# tm4cShield_v2_0.net
KiCad netlist of a schematic drawn in EAGLE
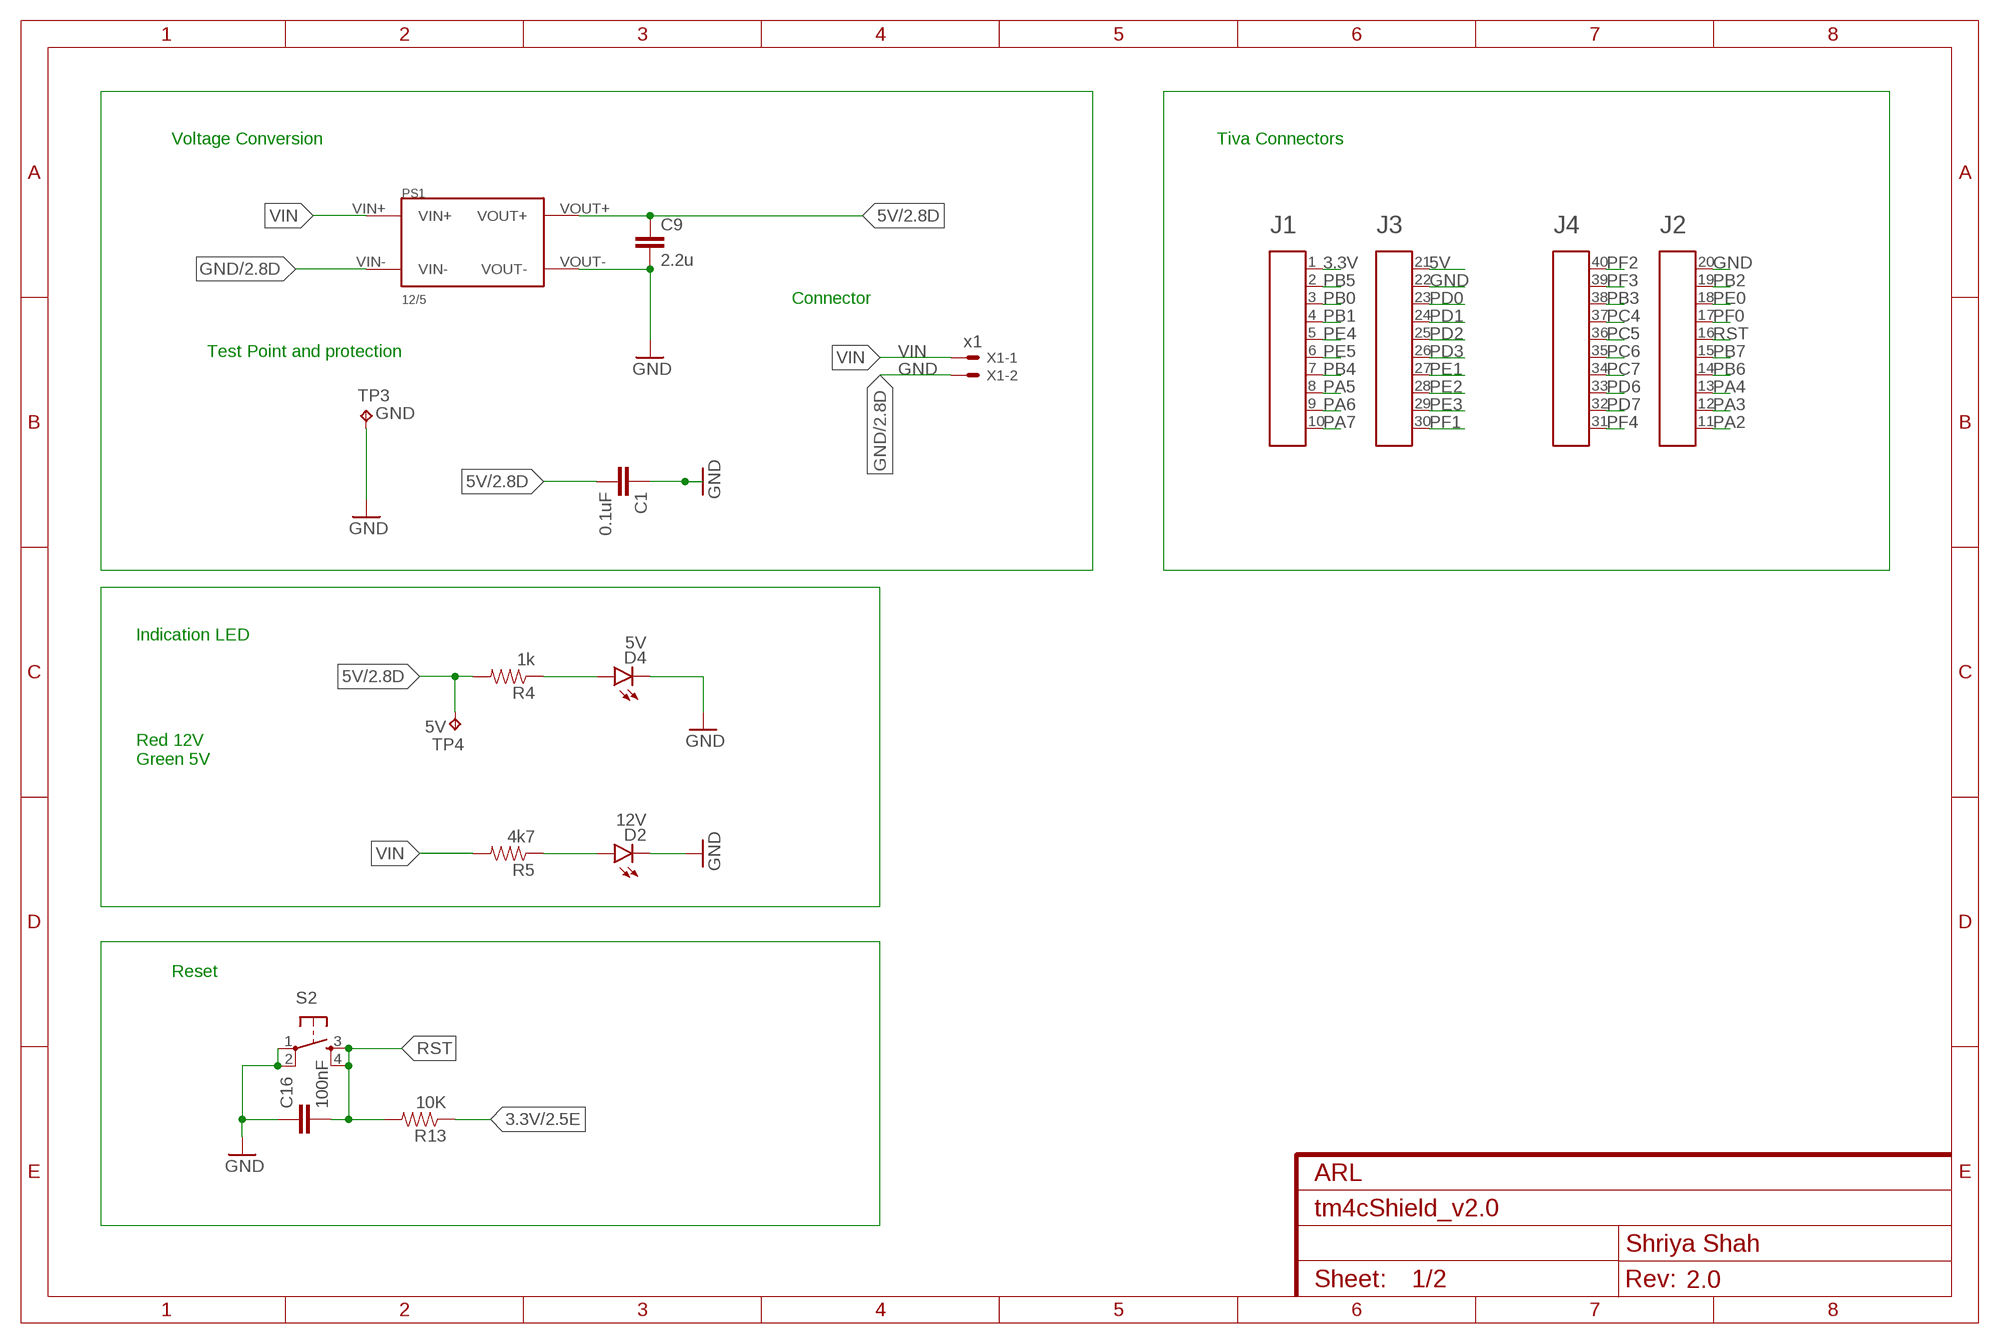
[diagram p0: schematic, sheet 1]
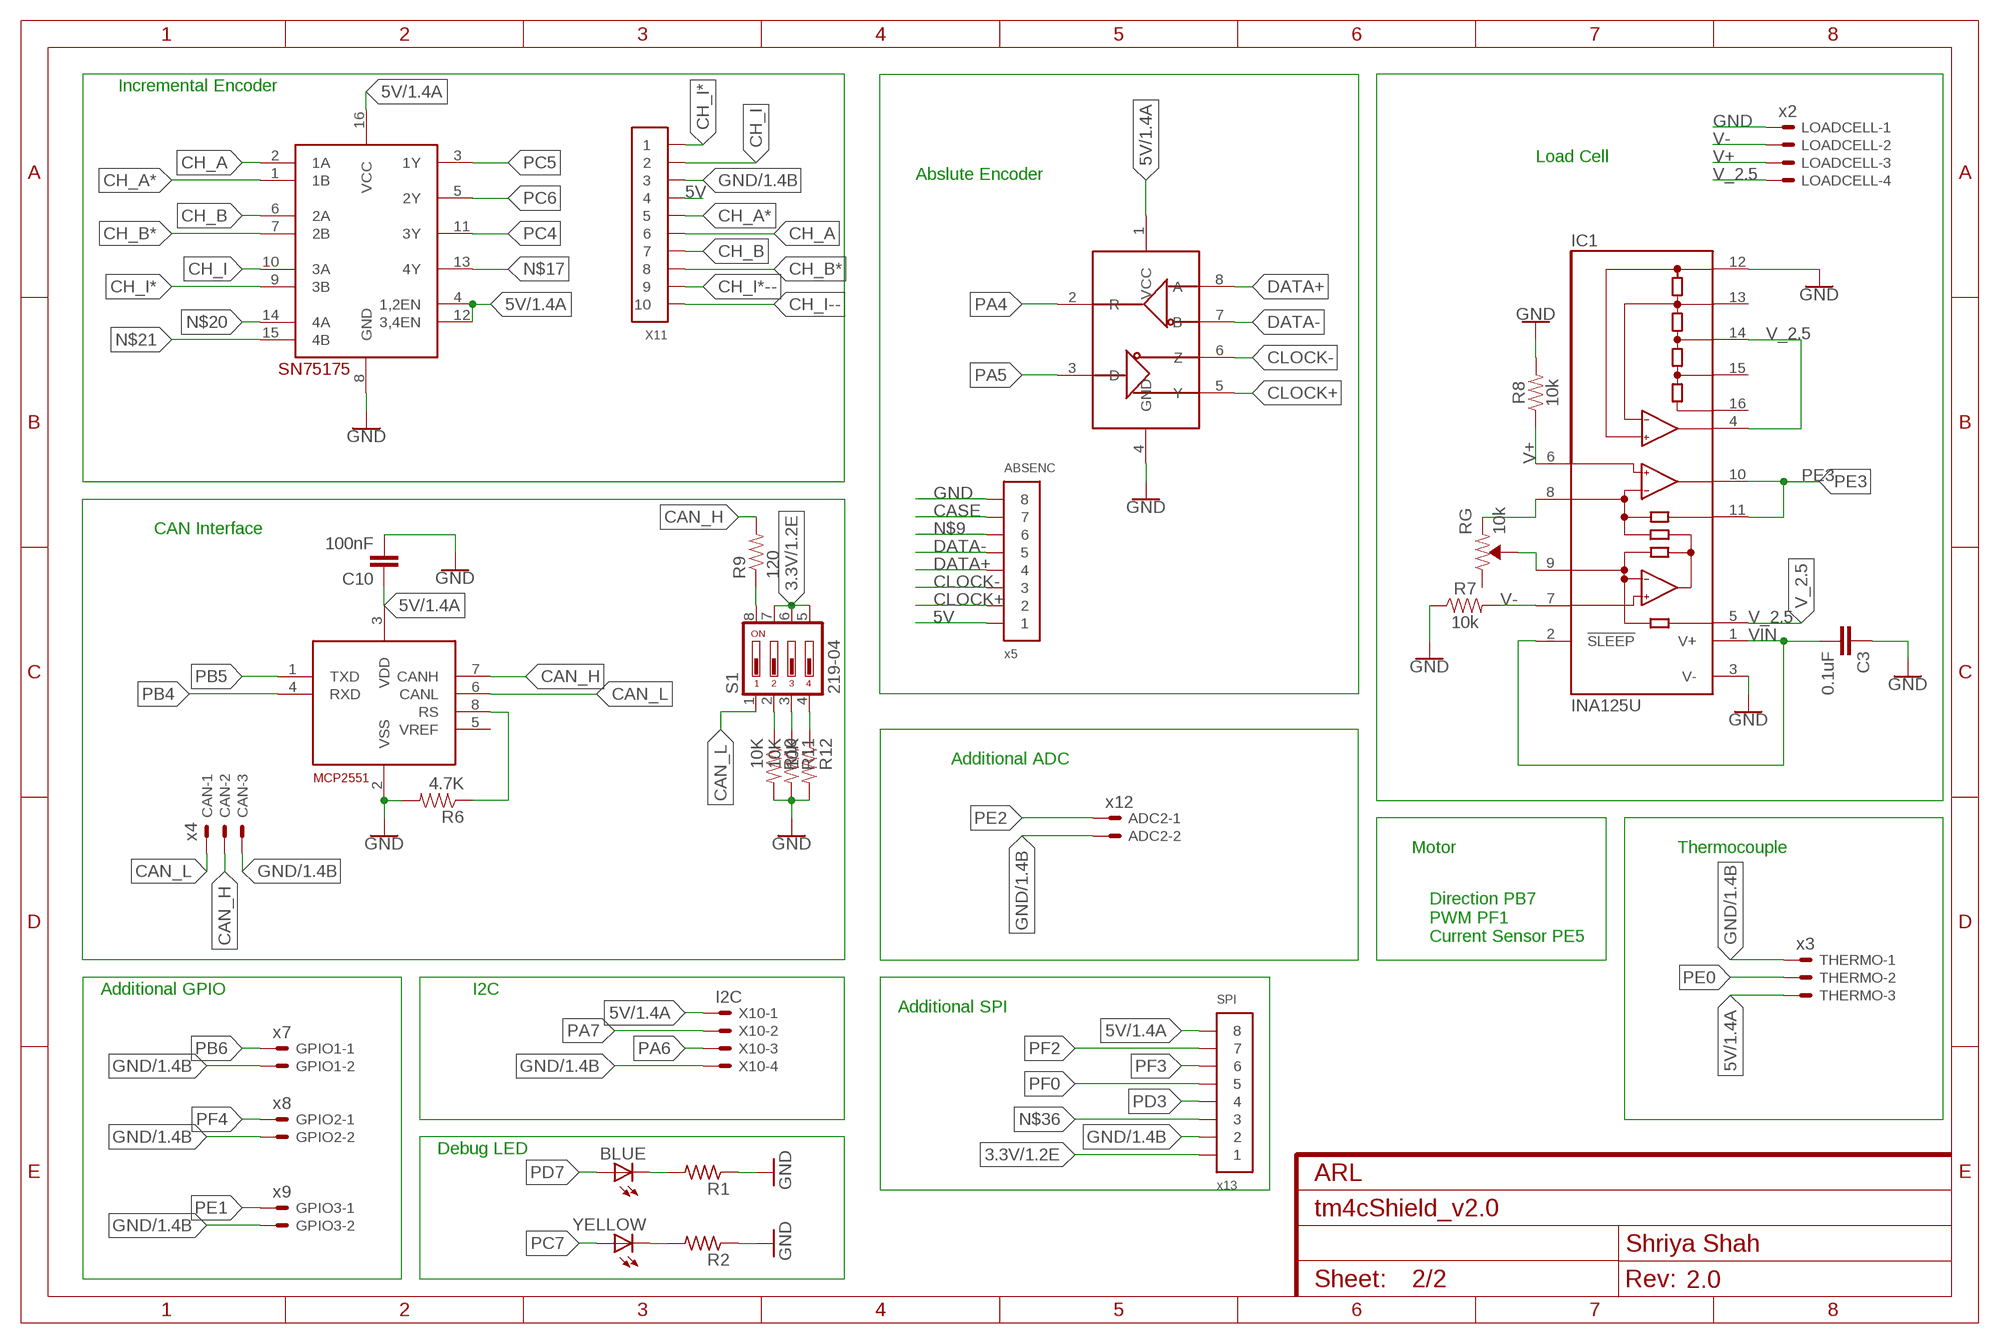
[diagram p1: schematic, sheet 2]

(export (version "E")
  (design (tool "Eeschema 10.0.6"))
  (components
    (comp (ref "ABSENC")
      (value "x5")
      (footprint "eagle-import:PB-53261-08")
      (fields (field (name "PARTNO") "0532610871"))
      (libsource (lib "eagle-import") (part "CONN_8-1-53261"))
    )
    (comp (ref "ADC2")
      (value "x12")
      (footprint "eagle-import:53261-02")
      (libsource (lib "eagle-import") (part "53?-02261"))
    )
    (comp (ref "BLUE")
      (value "LED0603")
      (footprint "eagle-import:LED-0603")
      (libsource (lib "eagle-import") (part "LED0603"))
    )
    (comp (ref "C3")
      (value "0.1uF")
      (footprint "eagle-import:0603")
      (libsource (lib "eagle-import") (part "0.1UF-0603-25V-(+80/-20%)"))
    )
    (comp (ref "C10")
      (value "100nF")
      (footprint "eagle-import:0603-CAP")
      (fields (field (name "PARTNO") "C1608X7R1E104K"))
      (libsource (lib "eagle-import") (part "CAP0603-CAP"))
    )
    (comp (ref "CAN")
      (value "x4")
      (footprint "eagle-import:53261-03")
      (fields (field (name "MF") "MOLEX") (field (name "MPN") "53261-0390"))
      (libsource (lib "eagle-import") (part "53?-03261"))
    )
    (comp (ref "GPIO1")
      (value "x7")
      (footprint "eagle-import:53261-02")
      (libsource (lib "eagle-import") (part "53?-02261"))
    )
    (comp (ref "GPIO2")
      (value "x8")
      (footprint "eagle-import:53261-02")
      (libsource (lib "eagle-import") (part "53?-02261"))
    )
    (comp (ref "GPIO3")
      (value "x9")
      (footprint "eagle-import:53261-02")
      (libsource (lib "eagle-import") (part "53?-02261"))
    )
    (comp (ref "IC1")
      (value "INA125U")
      (footprint "eagle-import:SO16-1")
      (fields (field (name "MF") "TEXAS INSTRUMENT CONNECTORS"))
      (libsource (lib "eagle-import") (part "INA125U"))
    )
    (comp (ref "IC2")
      (value "SP490")
      (footprint "eagle-import:SOIC8")
      (fields (field (name "PARTNO") "SP490CN-L"))
      (libsource (lib "eagle-import") (part "SP490"))
    )
    (comp (ref "IC3")
      (value "SN75175")
      (footprint "eagle-import:SOIC16")
      (fields (field (name "PARTNO") "SN75175DR"))
      (libsource (lib "eagle-import") (part "SN75175"))
    )
    (comp (ref "IC4")
      (value "MCP2551")
      (footprint "eagle-import:SOIC8")
      (fields (field (name "PARTNO") "MCP2551-I/SN"))
      (libsource (lib "eagle-import") (part "MCP2551"))
    )
    (comp (ref "LOADCELL")
      (value "x2")
      (footprint "eagle-import:53261-04")
      (libsource (lib "eagle-import") (part "53?-04261"))
    )
    (comp (ref "R1")
      (value "RESISTOR_0603")
      (footprint "eagle-import:RESC0603")
      (libsource (lib "eagle-import") (part "RESISTOR_0603"))
    )
    (comp (ref "R2")
      (value "RESISTOR_0603")
      (footprint "eagle-import:RESC0603")
      (libsource (lib "eagle-import") (part "RESISTOR_0603"))
    )
    (comp (ref "R6")
      (value "4.7K")
      (footprint "eagle-import:0603-RES")
      (fields (field (name "PARTNO") "ERJ-3EKF4701V"))
      (libsource (lib "eagle-import") (part "RESISTOR0603-RES"))
    )
    (comp (ref "R7")
      (value "10k")
      (footprint "eagle-import:0603")
      (libsource (lib "eagle-import") (part "0.05OHM-0603-1/5W-1%"))
    )
    (comp (ref "R8")
      (value "10k")
      (footprint "eagle-import:0603")
      (libsource (lib "eagle-import") (part "0.05OHM-0603-1/5W-1%"))
    )
    (comp (ref "R9")
      (value "120")
      (footprint "eagle-import:0603-RES")
      (fields (field (name "PARTNO") "ERJ-3GEYJ121V"))
      (libsource (lib "eagle-import") (part "RESISTOR0603-RES"))
    )
    (comp (ref "R10")
      (value "10K")
      (footprint "eagle-import:0603-RES")
      (fields (field (name "PARTNO") "ERJ-3EKF1002V"))
      (libsource (lib "eagle-import") (part "RESISTOR0603-RES"))
    )
    (comp (ref "R11")
      (value "10K")
      (footprint "eagle-import:0603-RES")
      (fields (field (name "PARTNO") "ERJ-3EKF1002V"))
      (libsource (lib "eagle-import") (part "RESISTOR0603-RES"))
    )
    (comp (ref "R12")
      (value "10K")
      (footprint "eagle-import:0603-RES")
      (fields (field (name "PARTNO") "ERJ-3EKF1002V"))
      (libsource (lib "eagle-import") (part "RESISTOR0603-RES"))
    )
    (comp (ref "RG")
      (value "10k")
      (footprint "eagle-import:TRIMPOT-PTH-3386U")
      (libsource (lib "eagle-import") (part "TRIMPOT-PTH-10MM-KNOB-1/2W-10%"))
    )
    (comp (ref "S1")
      (value "219-04")
      (footprint "eagle-import:CTS-219-04")
      (fields (field (name "PARTNO") "219-4LPST"))
      (libsource (lib "eagle-import") (part "219-04"))
    )
    (comp (ref "SPI")
      (value "x13")
      (footprint "eagle-import:PB-53261-08")
      (fields (field (name "PARTNO") "0532610871"))
      (libsource (lib "eagle-import") (part "CONN_8-1-53261"))
    )
    (comp (ref "THERMO")
      (value "x3")
      (footprint "eagle-import:53261-03")
      (fields (field (name "MF") "MOLEX") (field (name "MPN") "53261-0390"))
      (libsource (lib "eagle-import") (part "53?-03261"))
    )
    (comp (ref "X10")
      (value "I2C")
      (footprint "eagle-import:53261-04")
      (libsource (lib "eagle-import") (part "53?-04261"))
    )
    (comp (ref "X11")
      (value "CONN_10-1-53261")
      (footprint "eagle-import:PB-53261-10")
      (fields (field (name "PARTNO") "0532611071"))
      (libsource (lib "eagle-import") (part "CONN_10-1-53261"))
    )
    (comp (ref "YELLOW")
      (value "LED0603")
      (footprint "eagle-import:LED-0603")
      (libsource (lib "eagle-import") (part "LED0603"))
    )
    (comp (ref "A1")
      (value "HEADER4X10-BOOSTERPACK")
      (footprint "eagle-import:4X10-BOOSTERPACK")
      (libsource (lib "eagle-import") (part "HEADER4X10-BOOSTERPACK"))
    )
    (comp (ref "C1")
      (value "0.1uF")
      (footprint "eagle-import:0603")
      (libsource (lib "eagle-import") (part "0.1UF-0603-25V-(+80/-20%)"))
    )
    (comp (ref "C9")
      (value "2.2u")
      (footprint "eagle-import:0603-CAP")
      (fields (field (name "MPN") "GRM188R61H225KE11D"))
      (libsource (lib "eagle-import") (part "2.2U_CAPACITOR_0603"))
    )
    (comp (ref "C16")
      (value "100nF")
      (footprint "eagle-import:0603-CAP")
      (fields (field (name "PARTNO") "C1608X7R1E104K"))
      (libsource (lib "eagle-import") (part "SparkFun-Passives_CAP0603-CAP"))
    )
    (comp (ref "D2")
      (value "12V")
      (footprint "eagle-import:LED-0603")
      (fields (field (name "MPN") "LY L296-Q2R2-26-Z"))
      (libsource (lib "eagle-import") (part "YELLOW_LED_0603"))
    )
    (comp (ref "D4")
      (value "5V")
      (footprint "eagle-import:LED-0603")
      (fields (field (name "MPN") "LB L293-M2P1-36-1-Z"))
      (libsource (lib "eagle-import") (part "BLUE_LED_0603"))
    )
    (comp (ref "PS1")
      (value "12/5")
      (footprint "eagle-import:MURATA_NMG")
      (fields (field (name "MPN") "NMG2405SC "))
      (libsource (lib "eagle-import") (part "MURATA_NMG2405SC"))
    )
    (comp (ref "R4")
      (value "1k")
      (footprint "eagle-import:0603-RES")
      (fields (field (name "MPN") "CRCW06031K00FKEA"))
      (libsource (lib "eagle-import") (part "1K_RESISTOR_0603"))
    )
    (comp (ref "R5")
      (value "4k7")
      (footprint "eagle-import:0603-RES")
      (fields (field (name "MPN") "CRCW06034K70FKEA"))
      (libsource (lib "eagle-import") (part "4K7_RESISTOR_0603"))
    )
    (comp (ref "R13")
      (value "10K")
      (footprint "eagle-import:0603-RES")
      (fields (field (name "PARTNO") "ERJ-3EKF1002V"))
      (libsource (lib "eagle-import") (part "SparkFun-Passives_RESISTOR0603-RES"))
    )
    (comp (ref "S2")
      (value "TAC_SWITCHPTH")
      (footprint "eagle-import:TACTILE-PTH")
      (fields (field (name "PARTNO") "B3F-1005"))
      (libsource (lib "eagle-import") (part "TAC_SWITCHPTH"))
    )
    (comp (ref "TP3")
      (value "GND")
      (footprint "eagle-import:5000_SERIES_TESTPOINT")
      (fields (field (name "MPN") "5002"))
      (libsource (lib "eagle-import") (part "TP5000"))
    )
    (comp (ref "TP4")
      (value "5V")
      (footprint "eagle-import:5000_SERIES_TESTPOINT")
      (fields (field (name "MPN") "5002"))
      (libsource (lib "eagle-import") (part "TP5000"))
    )
    (comp (ref "X1")
      (value "x1")
      (footprint "eagle-import:53261-02")
      (libsource (lib "eagle-import") (part "53?-02261"))
    )
  )
  (nets
    (net (code "1") (name "3.3V") (class "Default")
      (node (ref "A1") (pin "1") (pinfunction "P$1_1") (pintype "bidirectional"))
      (node (ref "R13") (pin "1") (pinfunction "1_1") (pintype "passive"))
      (node (ref "S1") (pin "5") (pinfunction "5_5") (pintype "passive"))
      (node (ref "S1") (pin "6") (pinfunction "6_6") (pintype "passive"))
      (node (ref "S1") (pin "7") (pinfunction "7_7") (pintype "passive"))
      (node (ref "SPI") (pin "1") (pinfunction "1_1") (pintype "bidirectional"))
    )
    (net (code "2") (name "5V") (class "Default")
      (node (ref "A1") (pin "21") (pinfunction "P$21_21") (pintype "bidirectional"))
      (node (ref "ABSENC") (pin "1") (pinfunction "1_1") (pintype "bidirectional"))
      (node (ref "C1") (pin "2") (pinfunction "2_2") (pintype "passive"))
      (node (ref "C10") (pin "1") (pinfunction "1_1") (pintype "passive"))
      (node (ref "C9") (pin "1") (pinfunction "1_1") (pintype "passive"))
      (node (ref "IC2") (pin "1") (pinfunction "VCC_1") (pintype "bidirectional"))
      (node (ref "IC3") (pin "12") (pinfunction "3,4EN_12") (pintype "bidirectional"))
      (node (ref "IC3") (pin "16") (pinfunction "VCC_16") (pintype "bidirectional"))
      (node (ref "IC3") (pin "4") (pinfunction "1,2EN_4") (pintype "bidirectional"))
      (node (ref "IC4") (pin "3") (pinfunction "VDD_3") (pintype "bidirectional"))
      (node (ref "PS1") (pin "VOUT+") (pinfunction "VOUT+_VOUT+") (pintype "bidirectional"))
      (node (ref "R4") (pin "2") (pinfunction "2_2") (pintype "passive"))
      (node (ref "SPI") (pin "8") (pinfunction "8_8") (pintype "bidirectional"))
      (node (ref "THERMO") (pin "3") (pinfunction "S_3") (pintype "passive"))
      (node (ref "TP4") (pin "P$1") (pinfunction "TP_P$1") (pintype "input"))
      (node (ref "X10") (pin "1") (pinfunction "S_1") (pintype "passive"))
      (node (ref "X11") (pin "4") (pinfunction "4_4") (pintype "bidirectional"))
    )
    (net (code "3") (name "CAN_H") (class "Default")
      (node (ref "CAN") (pin "2") (pinfunction "S_2") (pintype "passive"))
      (node (ref "IC4") (pin "7") (pinfunction "CANH_7") (pintype "bidirectional"))
      (node (ref "R9") (pin "2") (pinfunction "2_2") (pintype "passive"))
    )
    (net (code "4") (name "CAN_L") (class "Default")
      (node (ref "CAN") (pin "1") (pinfunction "S_1") (pintype "passive"))
      (node (ref "IC4") (pin "6") (pinfunction "CANL_6") (pintype "bidirectional"))
      (node (ref "S1") (pin "1") (pinfunction "1_1") (pintype "passive"))
    )
    (net (code "5") (name "CASE") (class "Default")
      (node (ref "ABSENC") (pin "7") (pinfunction "7_7") (pintype "bidirectional"))
    )
    (net (code "6") (name "CH_A") (class "Default")
      (node (ref "IC3") (pin "2") (pinfunction "1A_2") (pintype "bidirectional"))
      (node (ref "X11") (pin "6") (pinfunction "6_6") (pintype "bidirectional"))
    )
    (net (code "7") (name "CH_A*") (class "Default")
      (node (ref "IC3") (pin "1") (pinfunction "1B_1") (pintype "bidirectional"))
      (node (ref "X11") (pin "5") (pinfunction "5_5") (pintype "bidirectional"))
    )
    (net (code "8") (name "CH_B") (class "Default")
      (node (ref "IC3") (pin "6") (pinfunction "2A_6") (pintype "bidirectional"))
      (node (ref "X11") (pin "7") (pinfunction "7_7") (pintype "bidirectional"))
    )
    (net (code "9") (name "CH_B*") (class "Default")
      (node (ref "IC3") (pin "7") (pinfunction "2B_7") (pintype "bidirectional"))
      (node (ref "X11") (pin "8") (pinfunction "8_8") (pintype "bidirectional"))
    )
    (net (code "10") (name "CH_I") (class "Default")
      (node (ref "IC3") (pin "10") (pinfunction "3A_10") (pintype "bidirectional"))
      (node (ref "X11") (pin "2") (pinfunction "2_2") (pintype "bidirectional"))
    )
    (net (code "11") (name "CH_I*") (class "Default")
      (node (ref "IC3") (pin "9") (pinfunction "3B_9") (pintype "bidirectional"))
      (node (ref "X11") (pin "1") (pinfunction "1_1") (pintype "bidirectional"))
    )
    (net (code "12") (name "CH_I*--") (class "Default")
      (node (ref "X11") (pin "9") (pinfunction "9_9") (pintype "bidirectional"))
    )
    (net (code "13") (name "CH_I--") (class "Default")
      (node (ref "X11") (pin "10") (pinfunction "10_10") (pintype "bidirectional"))
    )
    (net (code "14") (name "CLOCK+") (class "Default")
      (node (ref "ABSENC") (pin "2") (pinfunction "2_2") (pintype "bidirectional"))
      (node (ref "IC2") (pin "5") (pinfunction "Y_5") (pintype "bidirectional"))
    )
    (net (code "15") (name "CLOCK-") (class "Default")
      (node (ref "ABSENC") (pin "3") (pinfunction "3_3") (pintype "bidirectional"))
      (node (ref "IC2") (pin "6") (pinfunction "Z_6") (pintype "bidirectional"))
    )
    (net (code "16") (name "DATA+") (class "Default")
      (node (ref "ABSENC") (pin "4") (pinfunction "4_4") (pintype "bidirectional"))
      (node (ref "IC2") (pin "8") (pinfunction "A_8") (pintype "bidirectional"))
    )
    (net (code "17") (name "DATA-") (class "Default")
      (node (ref "ABSENC") (pin "5") (pinfunction "5_5") (pintype "bidirectional"))
      (node (ref "IC2") (pin "7") (pinfunction "B_7") (pintype "bidirectional"))
    )
    (net (code "18") (name "GND") (class "Default")
      (node (ref "A1") (pin "20") (pinfunction "P$20_20") (pintype "bidirectional"))
      (node (ref "A1") (pin "22") (pinfunction "P$22_22") (pintype "bidirectional"))
      (node (ref "ABSENC") (pin "8") (pinfunction "8_8") (pintype "bidirectional"))
      (node (ref "ADC2") (pin "2") (pinfunction "S_2") (pintype "passive"))
      (node (ref "C1") (pin "1") (pinfunction "1_1") (pintype "passive"))
      (node (ref "C10") (pin "2") (pinfunction "2_2") (pintype "passive"))
      (node (ref "C16") (pin "1") (pinfunction "1_1") (pintype "passive"))
      (node (ref "C3") (pin "1") (pinfunction "1_1") (pintype "passive"))
      (node (ref "C9") (pin "2") (pinfunction "2_2") (pintype "passive"))
      (node (ref "CAN") (pin "3") (pinfunction "S_3") (pintype "passive"))
      (node (ref "D2") (pin "C") (pinfunction "C_C") (pintype "passive"))
      (node (ref "D4") (pin "C") (pinfunction "C_C") (pintype "passive"))
      (node (ref "GPIO1") (pin "2") (pinfunction "S_2") (pintype "passive"))
      (node (ref "GPIO2") (pin "2") (pinfunction "S_2") (pintype "passive"))
      (node (ref "GPIO3") (pin "2") (pinfunction "S_2") (pintype "passive"))
      (node (ref "IC1") (pin "12") (pinfunction "REFCOM_12") (pintype "passive"))
      (node (ref "IC1") (pin "3") (pinfunction "V-_3") (pintype "power_in"))
      (node (ref "IC2") (pin "4") (pinfunction "GND_4") (pintype "bidirectional"))
      (node (ref "IC3") (pin "8") (pinfunction "GND_8") (pintype "bidirectional"))
      (node (ref "IC4") (pin "2") (pinfunction "VSS_2") (pintype "bidirectional"))
      (node (ref "LOADCELL") (pin "1") (pinfunction "S_1") (pintype "passive"))
      (node (ref "PS1") (pin "VIN-") (pinfunction "VIN-_VIN-") (pintype "bidirectional"))
      (node (ref "PS1") (pin "VOUT-") (pinfunction "VOUT-_VOUT-") (pintype "bidirectional"))
      (node (ref "R1") (pin "1") (pinfunction "1_1") (pintype "passive"))
      (node (ref "R10") (pin "2") (pinfunction "2_2") (pintype "passive"))
      (node (ref "R11") (pin "2") (pinfunction "2_2") (pintype "passive"))
      (node (ref "R12") (pin "2") (pinfunction "2_2") (pintype "passive"))
      (node (ref "R2") (pin "1") (pinfunction "1_1") (pintype "passive"))
      (node (ref "R6") (pin "2") (pinfunction "2_2") (pintype "passive"))
      (node (ref "R7") (pin "1") (pinfunction "1_1") (pintype "passive"))
      (node (ref "R8") (pin "2") (pinfunction "2_2") (pintype "passive"))
      (node (ref "S2") (pin "1") (pinfunction "1_1") (pintype "passive"))
      (node (ref "S2") (pin "2") (pinfunction "2_2") (pintype "passive"))
      (node (ref "SPI") (pin "2") (pinfunction "2_2") (pintype "bidirectional"))
      (node (ref "THERMO") (pin "1") (pinfunction "S_1") (pintype "passive"))
      (node (ref "TP3") (pin "P$1") (pinfunction "TP_P$1") (pintype "input"))
      (node (ref "X1") (pin "2") (pinfunction "S_2") (pintype "passive"))
      (node (ref "X10") (pin "4") (pinfunction "S_4") (pintype "passive"))
      (node (ref "X11") (pin "3") (pinfunction "3_3") (pintype "bidirectional"))
    )
    (net (code "19") (name "N$9") (class "Default")
      (node (ref "ABSENC") (pin "6") (pinfunction "6_6") (pintype "bidirectional"))
    )
    (net (code "20") (name "N$17") (class "Default")
      (node (ref "IC3") (pin "13") (pinfunction "4Y_13") (pintype "bidirectional"))
    )
    (net (code "21") (name "N$20") (class "Default")
      (node (ref "IC3") (pin "14") (pinfunction "4A_14") (pintype "bidirectional"))
    )
    (net (code "22") (name "N$21") (class "Default")
      (node (ref "IC3") (pin "15") (pinfunction "4B_15") (pintype "bidirectional"))
    )
    (net (code "23") (name "N$36") (class "Default")
      (node (ref "SPI") (pin "3") (pinfunction "3_3") (pintype "bidirectional"))
    )
    (net (code "24") (name "Net-(BLUE-PadC)") (class "Default")
      (node (ref "BLUE") (pin "C") (pinfunction "C_C") (pintype "passive"))
      (node (ref "R1") (pin "2") (pinfunction "2_2") (pintype "passive"))
    )
    (net (code "25") (name "Net-(D2-PadA)") (class "Default")
      (node (ref "D2") (pin "A") (pinfunction "A_A") (pintype "passive"))
      (node (ref "R5") (pin "1") (pinfunction "1_1") (pintype "passive"))
    )
    (net (code "26") (name "Net-(D4-PadA)") (class "Default")
      (node (ref "D4") (pin "A") (pinfunction "A_A") (pintype "passive"))
      (node (ref "R4") (pin "1") (pinfunction "1_1") (pintype "passive"))
    )
    (net (code "27") (name "Net-(IC4-RS)") (class "Default")
      (node (ref "IC4") (pin "8") (pinfunction "RS_8") (pintype "bidirectional"))
      (node (ref "R6") (pin "1") (pinfunction "1_1") (pintype "passive"))
    )
    (net (code "28") (name "Net-(R2-Pad2)") (class "Default")
      (node (ref "R2") (pin "2") (pinfunction "2_2") (pintype "passive"))
      (node (ref "YELLOW") (pin "C") (pinfunction "C_C") (pintype "passive"))
    )
    (net (code "29") (name "Net-(R9-Pad1)") (class "Default")
      (node (ref "R9") (pin "1") (pinfunction "1_1") (pintype "passive"))
      (node (ref "S1") (pin "8") (pinfunction "8_8") (pintype "passive"))
    )
    (net (code "30") (name "Net-(R10-Pad1)") (class "Default")
      (node (ref "R10") (pin "1") (pinfunction "1_1") (pintype "passive"))
      (node (ref "S1") (pin "2") (pinfunction "2_2") (pintype "passive"))
    )
    (net (code "31") (name "Net-(R11-Pad1)") (class "Default")
      (node (ref "R11") (pin "1") (pinfunction "1_1") (pintype "passive"))
      (node (ref "S1") (pin "3") (pinfunction "3_3") (pintype "passive"))
    )
    (net (code "32") (name "Net-(R12-Pad1)") (class "Default")
      (node (ref "R12") (pin "1") (pinfunction "1_1") (pintype "passive"))
      (node (ref "S1") (pin "4") (pinfunction "4_4") (pintype "passive"))
    )
    (net (code "33") (name "Net-(RG-CCW)") (class "Default")
      (node (ref "IC1") (pin "8") (pinfunction "RG_8") (pintype "passive"))
      (node (ref "RG") (pin "1") (pinfunction "CCW_1") (pintype "passive"))
    )
    (net (code "34") (name "Net-(RG-WIPER)") (class "Default")
      (node (ref "IC1") (pin "9") (pinfunction "RG_9") (pintype "passive"))
      (node (ref "RG") (pin "2") (pinfunction "WIPER_2") (pintype "passive"))
    )
    (net (code "35") (name "PA2") (class "Default")
      (node (ref "A1") (pin "11") (pinfunction "P$11_11") (pintype "bidirectional"))
    )
    (net (code "36") (name "PA3") (class "Default")
      (node (ref "A1") (pin "12") (pinfunction "P$12_12") (pintype "bidirectional"))
    )
    (net (code "37") (name "PA4") (class "Default")
      (node (ref "A1") (pin "13") (pinfunction "P$13_13") (pintype "bidirectional"))
      (node (ref "IC2") (pin "2") (pinfunction "R_2") (pintype "bidirectional"))
    )
    (net (code "38") (name "PA5") (class "Default")
      (node (ref "A1") (pin "8") (pinfunction "P$8_8") (pintype "bidirectional"))
      (node (ref "IC2") (pin "3") (pinfunction "D_3") (pintype "bidirectional"))
    )
    (net (code "39") (name "PA6") (class "Default")
      (node (ref "A1") (pin "9") (pinfunction "P$9_9") (pintype "bidirectional"))
      (node (ref "X10") (pin "3") (pinfunction "S_3") (pintype "passive"))
    )
    (net (code "40") (name "PA7") (class "Default")
      (node (ref "A1") (pin "10") (pinfunction "P$10_10") (pintype "bidirectional"))
      (node (ref "X10") (pin "2") (pinfunction "S_2") (pintype "passive"))
    )
    (net (code "41") (name "PB0") (class "Default")
      (node (ref "A1") (pin "3") (pinfunction "P$3_3") (pintype "bidirectional"))
    )
    (net (code "42") (name "PB1") (class "Default")
      (node (ref "A1") (pin "4") (pinfunction "P$4_4") (pintype "bidirectional"))
    )
    (net (code "43") (name "PB2") (class "Default")
      (node (ref "A1") (pin "19") (pinfunction "P$19_19") (pintype "bidirectional"))
    )
    (net (code "44") (name "PB3") (class "Default")
      (node (ref "A1") (pin "38") (pinfunction "P$38_38") (pintype "bidirectional"))
    )
    (net (code "45") (name "PB4") (class "Default")
      (node (ref "A1") (pin "7") (pinfunction "P$7_7") (pintype "bidirectional"))
      (node (ref "IC4") (pin "4") (pinfunction "RXD_4") (pintype "bidirectional"))
    )
    (net (code "46") (name "PB5") (class "Default")
      (node (ref "A1") (pin "2") (pinfunction "P$2_2") (pintype "bidirectional"))
      (node (ref "IC4") (pin "1") (pinfunction "TXD_1") (pintype "bidirectional"))
    )
    (net (code "47") (name "PB6") (class "Default")
      (node (ref "A1") (pin "14") (pinfunction "P$14_14") (pintype "bidirectional"))
      (node (ref "GPIO1") (pin "1") (pinfunction "S_1") (pintype "passive"))
    )
    (net (code "48") (name "PB7") (class "Default")
      (node (ref "A1") (pin "15") (pinfunction "P$15_15") (pintype "bidirectional"))
    )
    (net (code "49") (name "PC4") (class "Default")
      (node (ref "A1") (pin "37") (pinfunction "P$37_37") (pintype "bidirectional"))
      (node (ref "IC3") (pin "11") (pinfunction "3Y_11") (pintype "bidirectional"))
    )
    (net (code "50") (name "PC5") (class "Default")
      (node (ref "A1") (pin "36") (pinfunction "P$36_36") (pintype "bidirectional"))
      (node (ref "IC3") (pin "3") (pinfunction "1Y_3") (pintype "bidirectional"))
    )
    (net (code "51") (name "PC6") (class "Default")
      (node (ref "A1") (pin "35") (pinfunction "P$35_35") (pintype "bidirectional"))
      (node (ref "IC3") (pin "5") (pinfunction "2Y_5") (pintype "bidirectional"))
    )
    (net (code "52") (name "PC7") (class "Default")
      (node (ref "A1") (pin "34") (pinfunction "P$34_34") (pintype "bidirectional"))
      (node (ref "YELLOW") (pin "A") (pinfunction "A_A") (pintype "passive"))
    )
    (net (code "53") (name "PD0") (class "Default")
      (node (ref "A1") (pin "23") (pinfunction "P$23_23") (pintype "bidirectional"))
    )
    (net (code "54") (name "PD1") (class "Default")
      (node (ref "A1") (pin "24") (pinfunction "P$24_24") (pintype "bidirectional"))
    )
    (net (code "55") (name "PD2") (class "Default")
      (node (ref "A1") (pin "25") (pinfunction "P$25_25") (pintype "bidirectional"))
    )
    (net (code "56") (name "PD3") (class "Default")
      (node (ref "A1") (pin "26") (pinfunction "P$26_26") (pintype "bidirectional"))
      (node (ref "SPI") (pin "4") (pinfunction "4_4") (pintype "bidirectional"))
    )
    (net (code "57") (name "PD6") (class "Default")
      (node (ref "A1") (pin "33") (pinfunction "P$33_33") (pintype "bidirectional"))
    )
    (net (code "58") (name "PD7") (class "Default")
      (node (ref "A1") (pin "32") (pinfunction "P$32_32") (pintype "bidirectional"))
      (node (ref "BLUE") (pin "A") (pinfunction "A_A") (pintype "passive"))
    )
    (net (code "59") (name "PE0") (class "Default")
      (node (ref "A1") (pin "18") (pinfunction "P$18_18") (pintype "bidirectional"))
      (node (ref "THERMO") (pin "2") (pinfunction "S_2") (pintype "passive"))
    )
    (net (code "60") (name "PE1") (class "Default")
      (node (ref "A1") (pin "27") (pinfunction "P$27_27") (pintype "bidirectional"))
      (node (ref "GPIO3") (pin "1") (pinfunction "S_1") (pintype "passive"))
    )
    (net (code "61") (name "PE2") (class "Default")
      (node (ref "A1") (pin "28") (pinfunction "P$28_28") (pintype "bidirectional"))
      (node (ref "ADC2") (pin "1") (pinfunction "S_1") (pintype "passive"))
    )
    (net (code "62") (name "PE3") (class "Default")
      (node (ref "A1") (pin "29") (pinfunction "P$29_29") (pintype "bidirectional"))
      (node (ref "IC1") (pin "10") (pinfunction "OUT_10") (pintype "output"))
      (node (ref "IC1") (pin "11") (pinfunction "SENSE_11") (pintype "passive"))
    )
    (net (code "63") (name "PE4") (class "Default")
      (node (ref "A1") (pin "5") (pinfunction "P$5_5") (pintype "bidirectional"))
    )
    (net (code "64") (name "PE5") (class "Default")
      (node (ref "A1") (pin "6") (pinfunction "P$6_6") (pintype "bidirectional"))
    )
    (net (code "65") (name "PF0") (class "Default")
      (node (ref "A1") (pin "17") (pinfunction "P$17_17") (pintype "bidirectional"))
      (node (ref "SPI") (pin "5") (pinfunction "5_5") (pintype "bidirectional"))
    )
    (net (code "66") (name "PF1") (class "Default")
      (node (ref "A1") (pin "30") (pinfunction "P$30_30") (pintype "bidirectional"))
    )
    (net (code "67") (name "PF2") (class "Default")
      (node (ref "A1") (pin "40") (pinfunction "P$40_40") (pintype "bidirectional"))
      (node (ref "SPI") (pin "7") (pinfunction "7_7") (pintype "bidirectional"))
    )
    (net (code "68") (name "PF3") (class "Default")
      (node (ref "A1") (pin "39") (pinfunction "P$39_39") (pintype "bidirectional"))
      (node (ref "SPI") (pin "6") (pinfunction "6_6") (pintype "bidirectional"))
    )
    (net (code "69") (name "PF4") (class "Default")
      (node (ref "A1") (pin "31") (pinfunction "P$31_31") (pintype "bidirectional"))
      (node (ref "GPIO2") (pin "1") (pinfunction "S_1") (pintype "passive"))
    )
    (net (code "70") (name "RST") (class "Default")
      (node (ref "A1") (pin "16") (pinfunction "P$16_16") (pintype "bidirectional"))
      (node (ref "C16") (pin "2") (pinfunction "2_2") (pintype "passive"))
      (node (ref "R13") (pin "2") (pinfunction "2_2") (pintype "passive"))
      (node (ref "S2") (pin "3") (pinfunction "3_3") (pintype "passive"))
      (node (ref "S2") (pin "4") (pinfunction "4_4") (pintype "passive"))
    )
    (net (code "71") (name "V+") (class "Default")
      (node (ref "IC1") (pin "6") (pinfunction "+IN_6") (pintype "input"))
      (node (ref "LOADCELL") (pin "3") (pinfunction "S_3") (pintype "passive"))
      (node (ref "R8") (pin "1") (pinfunction "1_1") (pintype "passive"))
    )
    (net (code "72") (name "V-") (class "Default")
      (node (ref "IC1") (pin "7") (pinfunction "-IN_7") (pintype "input"))
      (node (ref "LOADCELL") (pin "2") (pinfunction "S_2") (pintype "passive"))
      (node (ref "R7") (pin "2") (pinfunction "2_2") (pintype "passive"))
    )
    (net (code "73") (name "VIN") (class "Default")
      (node (ref "C3") (pin "2") (pinfunction "2_2") (pintype "passive"))
      (node (ref "IC1") (pin "1") (pinfunction "V+_1") (pintype "power_in"))
      (node (ref "IC1") (pin "2") (pinfunction "~{SLEEP}_2") (pintype "input"))
      (node (ref "PS1") (pin "VIN+") (pinfunction "VIN+_VIN+") (pintype "bidirectional"))
      (node (ref "R5") (pin "2") (pinfunction "2_2") (pintype "passive"))
      (node (ref "X1") (pin "1") (pinfunction "S_1") (pintype "passive"))
    )
    (net (code "74") (name "V_2.5") (class "Default")
      (node (ref "IC1") (pin "14") (pinfunction "REF2.5_14") (pintype "output"))
      (node (ref "IC1") (pin "4") (pinfunction "REFOUT_4") (pintype "output"))
      (node (ref "IC1") (pin "5") (pinfunction "REF_5") (pintype "passive"))
      (node (ref "LOADCELL") (pin "4") (pinfunction "S_4") (pintype "passive"))
    )
    (net (code "75") (name "unconnected-(IC1-REF5-Pad15)") (class "Default")
      (node (ref "IC1") (pin "15") (pinfunction "REF5_15") (pintype "output"))
    )
    (net (code "76") (name "unconnected-(IC1-REF10-Pad16)") (class "Default")
      (node (ref "IC1") (pin "16") (pinfunction "REF10_16") (pintype "output"))
    )
    (net (code "77") (name "unconnected-(IC1-REFBG-Pad13)") (class "Default")
      (node (ref "IC1") (pin "13") (pinfunction "REFBG_13") (pintype "output"))
    )
    (net (code "78") (name "unconnected-(IC4-VREF-Pad5)") (class "Default")
      (node (ref "IC4") (pin "5") (pinfunction "VREF_5") (pintype "bidirectional"))
    )
    (net (code "79") (name "unconnected-(RG-CW-Pad3)") (class "Default")
      (node (ref "RG") (pin "3") (pinfunction "CW_3") (pintype "passive"))
    )
  )
)
